# Adafruit_ESP32_Feather_V2.net
KiCad netlist of a schematic drawn in EAGLE
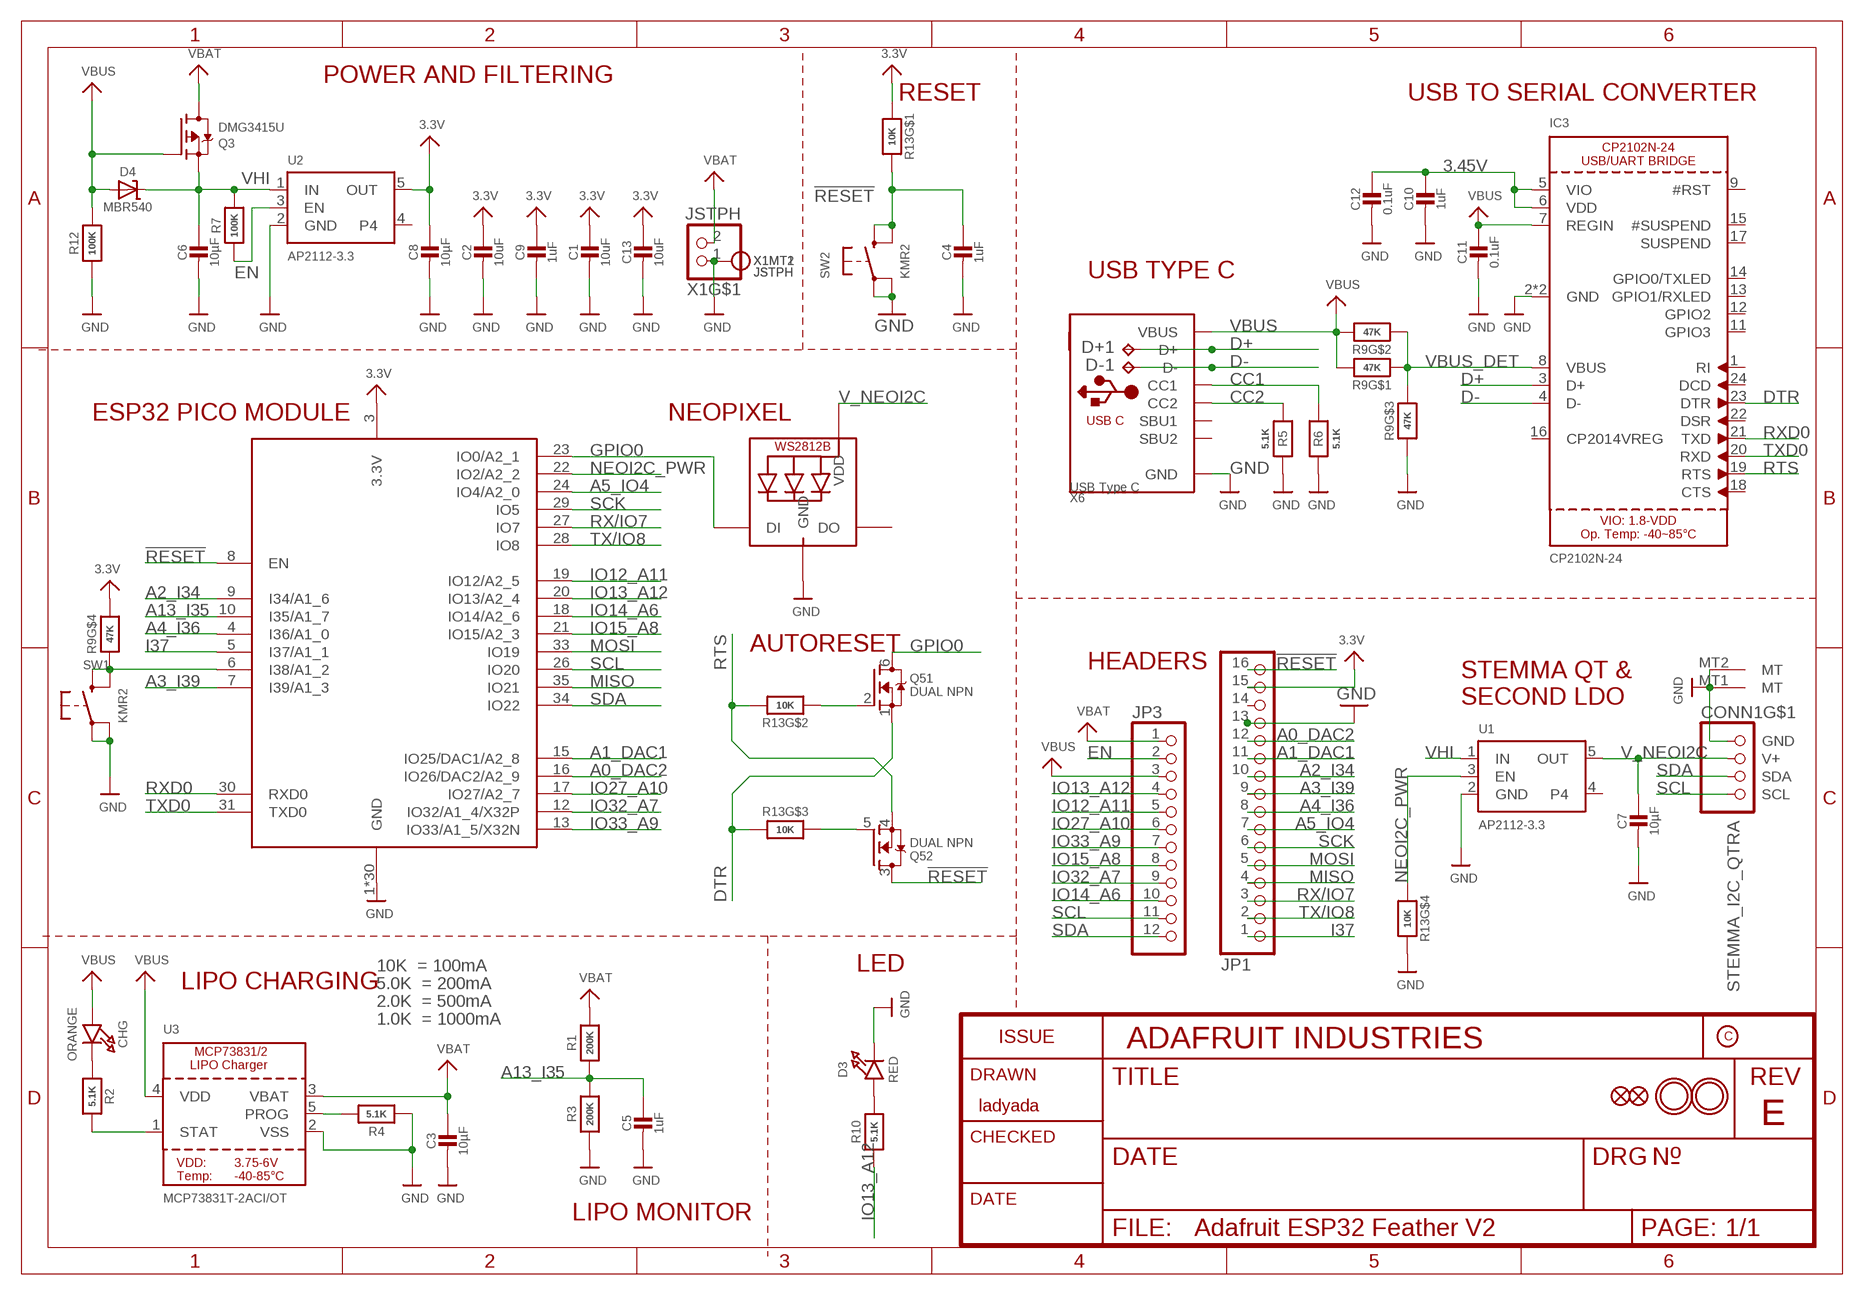
[diagram p0: schematic, sheet 1]

(export (version "E")
  (design (tool "Eeschema 10.0.6"))
  (components
    (comp (ref "C1")
      (value "10uF")
      (footprint "eagle-import:0805-NO")
      (libsource (lib "eagle-import") (part "CAP_CERAMIC0805-NOOUTLINE"))
    )
    (comp (ref "C2")
      (value "10uF")
      (footprint "eagle-import:0805-NO")
      (libsource (lib "eagle-import") (part "CAP_CERAMIC0805-NOOUTLINE"))
    )
    (comp (ref "C3")
      (value "10µF")
      (footprint "eagle-import:0805-NO")
      (libsource (lib "eagle-import") (part "CAP_CERAMIC0805-NOOUTLINE"))
    )
    (comp (ref "C4")
      (value "1uF")
      (footprint "eagle-import:0603-NO")
      (libsource (lib "eagle-import") (part "CAP_CERAMIC0603_NO"))
    )
    (comp (ref "C5")
      (value "1uF")
      (footprint "eagle-import:0603-NO")
      (libsource (lib "eagle-import") (part "CAP_CERAMIC0603_NO"))
    )
    (comp (ref "C6")
      (value "10µF")
      (footprint "eagle-import:0805-NO")
      (libsource (lib "eagle-import") (part "CAP_CERAMIC0805-NOOUTLINE"))
    )
    (comp (ref "C7")
      (value "10µF")
      (footprint "eagle-import:0805-NO")
      (libsource (lib "eagle-import") (part "CAP_CERAMIC0805-NOOUTLINE"))
    )
    (comp (ref "C8")
      (value "10µF")
      (footprint "eagle-import:0805-NO")
      (fields (field (name "REV") "F"))
      (libsource (lib "eagle-import") (part "CAP_CERAMIC0805-NOOUTLINE"))
    )
    (comp (ref "C9")
      (value "1uF")
      (footprint "eagle-import:0603-NO")
      (libsource (lib "eagle-import") (part "CAP_CERAMIC0603_NO"))
    )
    (comp (ref "C10")
      (value "1uF")
      (footprint "eagle-import:0603-NO")
      (libsource (lib "eagle-import") (part "CAP_CERAMIC0603_NO"))
    )
    (comp (ref "C11")
      (value "0.1uF")
      (footprint "eagle-import:0603-NO")
      (libsource (lib "eagle-import") (part "CAP_CERAMIC0603_NO"))
    )
    (comp (ref "C12")
      (value "0.1uF")
      (footprint "eagle-import:0603-NO")
      (libsource (lib "eagle-import") (part "CAP_CERAMIC0603_NO"))
    )
    (comp (ref "C13")
      (value "10uF")
      (footprint "eagle-import:0805-NO")
      (libsource (lib "eagle-import") (part "CAP_CERAMIC0805-NOOUTLINE"))
    )
    (comp (ref "CHG")
      (value "ORANGE")
      (footprint "eagle-import:CHIPLED_0603_NOOUTLINE")
      (libsource (lib "eagle-import") (part "LED0603_NOOUTLINE"))
    )
    (comp (ref "CONN1")
      (value "STEMMA_I2C_QTRA")
      (footprint "eagle-import:JST_SH4_RA")
      (libsource (lib "eagle-import") (part "STEMMA_I2C_QTRA"))
    )
    (comp (ref "D+1")
      (value "TPB1,27")
      (footprint "eagle-import:B1,27")
      (libsource (lib "eagle-import") (part "TPB1,27"))
    )
    (comp (ref "D-1")
      (value "TPB1,27")
      (footprint "eagle-import:B1,27")
      (libsource (lib "eagle-import") (part "TPB1,27"))
    )
    (comp (ref "D3")
      (value "RED")
      (footprint "eagle-import:CHIPLED_0603_NOOUTLINE")
      (libsource (lib "eagle-import") (part "LED0603_NOOUTLINE"))
    )
    (comp (ref "D4")
      (value "MBR540")
      (footprint "eagle-import:SOD-123")
      (libsource (lib "eagle-import") (part "DIODE-SCHOTTKYSOD-123"))
    )
    (comp (ref "IC3")
      (value "CP2102N-24")
      (footprint "eagle-import:QFN24_4MM_SMSC")
      (libsource (lib "eagle-import") (part "CP2102N-24"))
    )
    (comp (ref "JP1")
      (value "HEADER-1X16ROUND")
      (footprint "eagle-import:1X16_ROUND")
      (libsource (lib "eagle-import") (part "HEADER-1X16ROUND"))
    )
    (comp (ref "JP3")
      (value "HEADER-1X12")
      (footprint "eagle-import:1X12_ROUND")
      (libsource (lib "eagle-import") (part "HEADER-1X12"))
    )
    (comp (ref "LED1")
      (value "WS2812B3535")
      (footprint "eagle-import:LED3535")
      (libsource (lib "eagle-import") (part "WS2812B3535"))
    )
    (comp (ref "Q3")
      (value "DMG3415U")
      (footprint "eagle-import:SOT23-R")
      (libsource (lib "eagle-import") (part "MOSFET-P"))
    )
    (comp (ref "Q5")
      (value "DUAL NPN")
      (footprint "eagle-import:SOT363")
      (libsource (lib "eagle-import") (part "MOSFET-N_DUAL"))
    )
    (comp (ref "R1")
      (value "200K")
      (footprint "eagle-import:0603-NO")
      (libsource (lib "eagle-import") (part "RESISTOR_0603_NOOUT"))
    )
    (comp (ref "R2")
      (value "5.1K")
      (footprint "eagle-import:0603-NO")
      (libsource (lib "eagle-import") (part "RESISTOR_0603_NOOUT"))
    )
    (comp (ref "R3")
      (value "200K")
      (footprint "eagle-import:0603-NO")
      (libsource (lib "eagle-import") (part "RESISTOR_0603_NOOUT"))
    )
    (comp (ref "R4")
      (value "5.1K")
      (footprint "eagle-import:0603-NO")
      (libsource (lib "eagle-import") (part "RESISTOR_0603_NOOUT"))
    )
    (comp (ref "R5")
      (value "5.1K")
      (footprint "eagle-import:0603-NO")
      (libsource (lib "eagle-import") (part "RESISTOR_0603_NOOUT"))
    )
    (comp (ref "R6")
      (value "5.1K")
      (footprint "eagle-import:0603-NO")
      (libsource (lib "eagle-import") (part "RESISTOR_0603_NOOUT"))
    )
    (comp (ref "R7")
      (value "100K")
      (footprint "eagle-import:0603-NO")
      (libsource (lib "eagle-import") (part "RESISTOR_0603_NOOUT"))
    )
    (comp (ref "R9")
      (value "47K")
      (footprint "eagle-import:RESPACK_4X0603")
      (libsource (lib "eagle-import") (part "RESISTOR_4PACK"))
    )
    (comp (ref "R10")
      (value "5.1K")
      (footprint "eagle-import:0603-NO")
      (libsource (lib "eagle-import") (part "RESISTOR_0603_NOOUT"))
    )
    (comp (ref "R12")
      (value "100K")
      (footprint "eagle-import:0603-NO")
      (libsource (lib "eagle-import") (part "RESISTOR_0603_NOOUT"))
    )
    (comp (ref "R13")
      (value "10K")
      (footprint "eagle-import:RESPACK_4X0603")
      (libsource (lib "eagle-import") (part "RESISTOR_4PACK"))
    )
    (comp (ref "SW1")
      (value "KMR2")
      (footprint "eagle-import:BTN_KMR2_4.6X2.8")
      (libsource (lib "eagle-import") (part "SWITCH_TACT_SMT4.6X2.8"))
    )
    (comp (ref "SW2")
      (value "KMR2")
      (footprint "eagle-import:BTN_KMR2_4.6X2.8")
      (libsource (lib "eagle-import") (part "SWITCH_TACT_SMT4.6X2.8"))
    )
    (comp (ref "U$31")
      (value "MOUNTINGHOLE2.5")
      (footprint "eagle-import:MOUNTINGHOLE_2.5_PLATED")
      (libsource (lib "eagle-import") (part "MOUNTINGHOLE2.5"))
    )
    (comp (ref "U$32")
      (value "MOUNTINGHOLE2.5")
      (footprint "eagle-import:MOUNTINGHOLE_2.5_PLATED")
      (libsource (lib "eagle-import") (part "MOUNTINGHOLE2.5"))
    )
    (comp (ref "U$34")
      (value "FIDUCIAL_1MM")
      (footprint "eagle-import:FIDUCIAL_1MM")
      (libsource (lib "eagle-import") (part "FIDUCIAL_1MM"))
    )
    (comp (ref "U$35")
      (value "FIDUCIAL_1MM")
      (footprint "eagle-import:FIDUCIAL_1MM")
      (libsource (lib "eagle-import") (part "FIDUCIAL_1MM"))
    )
    (comp (ref "U1")
      (value "AP2112-3.3")
      (footprint "eagle-import:SOT23-5")
      (libsource (lib "eagle-import") (part "VREG_SOT23-5"))
    )
    (comp (ref "U2")
      (value "AP2112-3.3")
      (footprint "eagle-import:SOT23-5")
      (libsource (lib "eagle-import") (part "VREG_SOT23-5"))
    )
    (comp (ref "U3")
      (value "MCP73831T-2ACI/OT")
      (footprint "eagle-import:SOT23-5")
      (libsource (lib "eagle-import") (part "MCP73831/2"))
    )
    (comp (ref "X1")
      (value "JSTPH")
      (footprint "eagle-import:JSTPH2_BATT")
      (libsource (lib "eagle-import") (part "CON_JST_PH_2PIN_MT_BATT"))
    )
    (comp (ref "X3")
      (value "ESP32-PICO-MINI-02MINI")
      (footprint "eagle-import:ESP32-PICO-MINI")
      (libsource (lib "eagle-import") (part "ESP32-PICO-MINI-02MINI"))
    )
    (comp (ref "X6")
      (value "USB Type C")
      (footprint "eagle-import:USB_C_CUSB31-CFM2AX-01-X")
      (libsource (lib "eagle-import") (part "USB_C"))
    )
  )
  (nets
    (net (code "1") (name "/3.45V") (class "Default")
      (node (ref "C10") (pin "1") (pinfunction "1_1") (pintype "passive"))
      (node (ref "C12") (pin "1") (pinfunction "1_1") (pintype "passive"))
      (node (ref "IC3") (pin "5") (pinfunction "VIO_5") (pintype "power_in"))
      (node (ref "IC3") (pin "6") (pinfunction "VDD_6") (pintype "power_in"))
    )
    (net (code "2") (name "/A0_DAC2") (class "Default")
      (node (ref "JP1") (pin "12") (pinfunction "12_12") (pintype "passive"))
      (node (ref "X3") (pin "16") (pinfunction "IO26/DAC2/A2_9_16") (pintype "bidirectional"))
    )
    (net (code "3") (name "/A1_DAC1") (class "Default")
      (node (ref "JP1") (pin "11") (pinfunction "11_11") (pintype "passive"))
      (node (ref "X3") (pin "15") (pinfunction "IO25/DAC1/A2_8_15") (pintype "bidirectional"))
    )
    (net (code "4") (name "/A2_I34") (class "Default")
      (node (ref "JP1") (pin "10") (pinfunction "10_10") (pintype "passive"))
      (node (ref "X3") (pin "9") (pinfunction "I34/A1_6_9") (pintype "input"))
    )
    (net (code "5") (name "/A3_I39") (class "Default")
      (node (ref "JP1") (pin "9") (pinfunction "9_9") (pintype "passive"))
      (node (ref "X3") (pin "7") (pinfunction "I39/A1_3_7") (pintype "input"))
    )
    (net (code "6") (name "/A4_I36") (class "Default")
      (node (ref "JP1") (pin "8") (pinfunction "8_8") (pintype "passive"))
      (node (ref "X3") (pin "4") (pinfunction "I36/A1_0_4") (pintype "input"))
    )
    (net (code "7") (name "/A5_IO4") (class "Default")
      (node (ref "JP1") (pin "7") (pinfunction "7_7") (pintype "passive"))
      (node (ref "X3") (pin "24") (pinfunction "IO4/A2_0_24") (pintype "bidirectional"))
    )
    (net (code "8") (name "/A13_I35") (class "Default")
      (node (ref "C5") (pin "1") (pinfunction "1_1") (pintype "passive"))
      (node (ref "R1") (pin "1") (pinfunction "1_1") (pintype "passive"))
      (node (ref "R3") (pin "2") (pinfunction "2_2") (pintype "passive"))
      (node (ref "X3") (pin "10") (pinfunction "I35/A1_7_10") (pintype "input"))
    )
    (net (code "9") (name "/CC1") (class "Default")
      (node (ref "R6") (pin "2") (pinfunction "2_2") (pintype "passive"))
      (node (ref "X6") (pin "A5") (pinfunction "CC1_A5") (pintype "bidirectional"))
    )
    (net (code "10") (name "/CC2") (class "Default")
      (node (ref "R5") (pin "2") (pinfunction "2_2") (pintype "passive"))
      (node (ref "X6") (pin "B5") (pinfunction "CC2_B5") (pintype "bidirectional"))
    )
    (net (code "11") (name "/D+") (class "Default")
      (node (ref "D+1") (pin "TP") (pinfunction "TP_TP") (pintype "input"))
      (node (ref "IC3") (pin "3") (pinfunction "D+_3") (pintype "bidirectional"))
      (node (ref "X6") (pin "A6") (pinfunction "D+_A6") (pintype "bidirectional"))
      (node (ref "X6") (pin "B6") (pinfunction "D+_B6") (pintype "bidirectional"))
    )
    (net (code "12") (name "/D-") (class "Default")
      (node (ref "D-1") (pin "TP") (pinfunction "TP_TP") (pintype "input"))
      (node (ref "IC3") (pin "4") (pinfunction "D-_4") (pintype "bidirectional"))
      (node (ref "X6") (pin "A7") (pinfunction "D-_A7") (pintype "bidirectional"))
      (node (ref "X6") (pin "B7") (pinfunction "D-_B7") (pintype "bidirectional"))
    )
    (net (code "13") (name "/DTR") (class "Default")
      (node (ref "IC3") (pin "23") (pinfunction "DTR_23") (pintype "output"))
      (node (ref "Q5") (pin "1") (pinfunction "S_1") (pintype "bidirectional"))
      (node (ref "R13") (pin "3") (pinfunction "1_3") (pintype "passive"))
    )
    (net (code "14") (name "/EN") (class "Default")
      (node (ref "JP3") (pin "2") (pinfunction "2_2") (pintype "passive"))
      (node (ref "R7") (pin "1") (pinfunction "1_1") (pintype "passive"))
      (node (ref "U2") (pin "3") (pinfunction "EN_3") (pintype "input"))
    )
    (net (code "15") (name "/GPIO0") (class "Default")
      (node (ref "LED1") (pin "1") (pinfunction "DI_1") (pintype "input"))
      (node (ref "Q5") (pin "6") (pinfunction "D_6") (pintype "bidirectional"))
      (node (ref "X3") (pin "23") (pinfunction "IO0/A2_1_23") (pintype "bidirectional"))
    )
    (net (code "16") (name "/I37") (class "Default")
      (node (ref "JP1") (pin "1") (pinfunction "1_1") (pintype "passive"))
      (node (ref "X3") (pin "5") (pinfunction "I37/A1_1_5") (pintype "input"))
    )
    (net (code "17") (name "/IO12_A11") (class "Default")
      (node (ref "JP3") (pin "5") (pinfunction "5_5") (pintype "passive"))
      (node (ref "X3") (pin "19") (pinfunction "IO12/A2_5_19") (pintype "bidirectional"))
    )
    (net (code "18") (name "/IO13_A12") (class "Default")
      (node (ref "JP3") (pin "4") (pinfunction "4_4") (pintype "passive"))
      (node (ref "R10") (pin "1") (pinfunction "1_1") (pintype "passive"))
      (node (ref "X3") (pin "20") (pinfunction "IO13/A2_4_20") (pintype "bidirectional"))
    )
    (net (code "19") (name "/IO14_A6") (class "Default")
      (node (ref "JP3") (pin "10") (pinfunction "10_10") (pintype "passive"))
      (node (ref "X3") (pin "18") (pinfunction "IO14/A2_6_18") (pintype "bidirectional"))
    )
    (net (code "20") (name "/IO15_A8") (class "Default")
      (node (ref "JP3") (pin "8") (pinfunction "8_8") (pintype "passive"))
      (node (ref "X3") (pin "21") (pinfunction "IO15/A2_3_21") (pintype "bidirectional"))
    )
    (net (code "21") (name "/IO27_A10") (class "Default")
      (node (ref "JP3") (pin "6") (pinfunction "6_6") (pintype "passive"))
      (node (ref "X3") (pin "17") (pinfunction "IO27/A2_7_17") (pintype "bidirectional"))
    )
    (net (code "22") (name "/IO32_A7") (class "Default")
      (node (ref "JP3") (pin "9") (pinfunction "9_9") (pintype "passive"))
      (node (ref "X3") (pin "12") (pinfunction "IO32/A1_4/X32P_12") (pintype "bidirectional"))
    )
    (net (code "23") (name "/IO33_A9") (class "Default")
      (node (ref "JP3") (pin "7") (pinfunction "7_7") (pintype "passive"))
      (node (ref "X3") (pin "13") (pinfunction "IO33/A1_5/X32N_13") (pintype "bidirectional"))
    )
    (net (code "24") (name "/MISO") (class "Default")
      (node (ref "JP1") (pin "4") (pinfunction "4_4") (pintype "passive"))
      (node (ref "X3") (pin "35") (pinfunction "IO21_35") (pintype "bidirectional"))
    )
    (net (code "25") (name "/MOSI") (class "Default")
      (node (ref "JP1") (pin "5") (pinfunction "5_5") (pintype "passive"))
      (node (ref "X3") (pin "33") (pinfunction "IO19_33") (pintype "bidirectional"))
    )
    (net (code "26") (name "/NEOI2C_PWR") (class "Default")
      (node (ref "R13") (pin "4") (pinfunction "1_4") (pintype "passive"))
      (node (ref "U1") (pin "3") (pinfunction "EN_3") (pintype "input"))
      (node (ref "X3") (pin "22") (pinfunction "IO2/A2_2_22") (pintype "bidirectional"))
    )
    (net (code "27") (name "/RTS") (class "Default")
      (node (ref "IC3") (pin "19") (pinfunction "RTS_19") (pintype "output"))
      (node (ref "Q5") (pin "4") (pinfunction "S_4") (pintype "bidirectional"))
      (node (ref "R13") (pin "7") (pinfunction "2_7") (pintype "passive"))
    )
    (net (code "28") (name "/RXD0") (class "Default")
      (node (ref "IC3") (pin "21") (pinfunction "TXD_21") (pintype "output"))
      (node (ref "X3") (pin "30") (pinfunction "RXD0_30") (pintype "input"))
    )
    (net (code "29") (name "/RX{slash}IO7") (class "Default")
      (node (ref "JP1") (pin "3") (pinfunction "3_3") (pintype "passive"))
      (node (ref "X3") (pin "27") (pinfunction "IO7_27") (pintype "bidirectional"))
    )
    (net (code "30") (name "/SCK") (class "Default")
      (node (ref "JP1") (pin "6") (pinfunction "6_6") (pintype "passive"))
      (node (ref "X3") (pin "29") (pinfunction "IO5_29") (pintype "bidirectional"))
    )
    (net (code "31") (name "/SCL") (class "Default")
      (node (ref "CONN1") (pin "4") (pinfunction "SCL_4") (pintype "passive"))
      (node (ref "JP3") (pin "11") (pinfunction "11_11") (pintype "passive"))
      (node (ref "X3") (pin "26") (pinfunction "IO20_26") (pintype "bidirectional"))
    )
    (net (code "32") (name "/SDA") (class "Default")
      (node (ref "CONN1") (pin "3") (pinfunction "SDA_3") (pintype "passive"))
      (node (ref "JP3") (pin "12") (pinfunction "12_12") (pintype "passive"))
      (node (ref "X3") (pin "34") (pinfunction "IO22_34") (pintype "bidirectional"))
    )
    (net (code "33") (name "/TXD0") (class "Default")
      (node (ref "IC3") (pin "20") (pinfunction "RXD_20") (pintype "input"))
      (node (ref "X3") (pin "31") (pinfunction "TXD0_31") (pintype "output"))
    )
    (net (code "34") (name "/TX{slash}IO8") (class "Default")
      (node (ref "JP1") (pin "2") (pinfunction "2_2") (pintype "passive"))
      (node (ref "X3") (pin "28") (pinfunction "IO8_28") (pintype "bidirectional"))
    )
    (net (code "35") (name "/VBUS_DET") (class "Default")
      (node (ref "IC3") (pin "8") (pinfunction "VBUS_8") (pintype "power_in"))
      (node (ref "R9") (pin "1") (pinfunction "1_1") (pintype "passive"))
      (node (ref "R9") (pin "2") (pinfunction "1_2") (pintype "passive"))
      (node (ref "R9") (pin "6") (pinfunction "2_6") (pintype "passive"))
    )
    (net (code "36") (name "/VHI") (class "Default")
      (node (ref "C6") (pin "1") (pinfunction "1_1") (pintype "passive"))
      (node (ref "D4") (pin "C") (pinfunction "C_C") (pintype "passive"))
      (node (ref "Q3") (pin "2") (pinfunction "S_2") (pintype "passive"))
      (node (ref "R7") (pin "2") (pinfunction "2_2") (pintype "passive"))
      (node (ref "U1") (pin "1") (pinfunction "IN_1") (pintype "power_in"))
      (node (ref "U2") (pin "1") (pinfunction "IN_1") (pintype "power_in"))
    )
    (net (code "37") (name "/V_NEOI2C") (class "Default")
      (node (ref "C7") (pin "1") (pinfunction "1_1") (pintype "passive"))
      (node (ref "CONN1") (pin "2") (pinfunction "V+_2") (pintype "passive"))
      (node (ref "LED1") (pin "2") (pinfunction "VDD_2") (pintype "power_in"))
      (node (ref "U1") (pin "5") (pinfunction "OUT_5") (pintype "power_in"))
    )
    (net (code "38") (name "/~{RESET}") (class "Default")
      (node (ref "C4") (pin "1") (pinfunction "1_1") (pintype "passive"))
      (node (ref "JP1") (pin "16") (pinfunction "16_16") (pintype "passive"))
      (node (ref "Q5") (pin "3") (pinfunction "D_3") (pintype "bidirectional"))
      (node (ref "R13") (pin "8") (pinfunction "2_8") (pintype "passive"))
      (node (ref "SW2") (pin "B") (pinfunction "S_B") (pintype "passive"))
      (node (ref "SW2") (pin "B'") (pinfunction "S1_B'") (pintype "passive"))
      (node (ref "X3") (pin "8") (pinfunction "EN_8") (pintype "input"))
    )
    (net (code "39") (name "3.3V") (class "Default")
      (node (ref "C1") (pin "1") (pinfunction "1_1") (pintype "passive"))
      (node (ref "C13") (pin "1") (pinfunction "1_1") (pintype "passive"))
      (node (ref "C2") (pin "1") (pinfunction "1_1") (pintype "passive"))
      (node (ref "C8") (pin "1") (pinfunction "1_1") (pintype "passive"))
      (node (ref "C9") (pin "1") (pinfunction "1_1") (pintype "passive"))
      (node (ref "JP1") (pin "15") (pinfunction "15_15") (pintype "passive"))
      (node (ref "R13") (pin "1") (pinfunction "1_1") (pintype "passive"))
      (node (ref "R9") (pin "5") (pinfunction "2_5") (pintype "passive"))
      (node (ref "U2") (pin "5") (pinfunction "OUT_5") (pintype "power_in"))
      (node (ref "X3") (pin "3") (pinfunction "3.3V_3") (pintype "passive"))
    )
    (net (code "40") (name "GND") (class "Default")
      (node (ref "C1") (pin "2") (pinfunction "2_2") (pintype "passive"))
      (node (ref "C10") (pin "2") (pinfunction "2_2") (pintype "passive"))
      (node (ref "C11") (pin "2") (pinfunction "2_2") (pintype "passive"))
      (node (ref "C12") (pin "2") (pinfunction "2_2") (pintype "passive"))
      (node (ref "C13") (pin "2") (pinfunction "2_2") (pintype "passive"))
      (node (ref "C2") (pin "2") (pinfunction "2_2") (pintype "passive"))
      (node (ref "C3") (pin "2") (pinfunction "2_2") (pintype "passive"))
      (node (ref "C4") (pin "2") (pinfunction "2_2") (pintype "passive"))
      (node (ref "C5") (pin "2") (pinfunction "2_2") (pintype "passive"))
      (node (ref "C6") (pin "2") (pinfunction "2_2") (pintype "passive"))
      (node (ref "C7") (pin "2") (pinfunction "2_2") (pintype "passive"))
      (node (ref "C8") (pin "2") (pinfunction "2_2") (pintype "passive"))
      (node (ref "C9") (pin "2") (pinfunction "2_2") (pintype "passive"))
      (node (ref "CONN1") (pin "1") (pinfunction "GND_1") (pintype "passive"))
      (node (ref "CONN1") (pin "MT1") (pinfunction "MT_MT1") (pintype "bidirectional"))
      (node (ref "CONN1") (pin "MT2") (pinfunction "MT_MT2") (pintype "bidirectional"))
      (node (ref "D3") (pin "C") (pinfunction "C_C") (pintype "passive"))
      (node (ref "IC3") (pin "2") (pinfunction "GND_2") (pintype "power_in"))
      (node (ref "IC3") (pin "THERM") (pinfunction "GND_THERM") (pintype "power_in"))
      (node (ref "JP1") (pin "13") (pinfunction "13_13") (pintype "passive"))
      (node (ref "LED1") (pin "4") (pinfunction "GND_4") (pintype "power_in"))
      (node (ref "R12") (pin "1") (pinfunction "1_1") (pintype "passive"))
      (node (ref "R13") (pin "5") (pinfunction "2_5") (pintype "passive"))
      (node (ref "R3") (pin "1") (pinfunction "1_1") (pintype "passive"))
      (node (ref "R4") (pin "1") (pinfunction "1_1") (pintype "passive"))
      (node (ref "R5") (pin "1") (pinfunction "1_1") (pintype "passive"))
      (node (ref "R6") (pin "1") (pinfunction "1_1") (pintype "passive"))
      (node (ref "R9") (pin "3") (pinfunction "1_3") (pintype "passive"))
      (node (ref "SW1") (pin "A") (pinfunction "P_A") (pintype "passive"))
      (node (ref "SW1") (pin "A'") (pinfunction "P1_A'") (pintype "passive"))
      (node (ref "SW2") (pin "A") (pinfunction "P_A") (pintype "passive"))
      (node (ref "SW2") (pin "A'") (pinfunction "P1_A'") (pintype "passive"))
      (node (ref "U1") (pin "2") (pinfunction "GND_2") (pintype "power_in"))
      (node (ref "U2") (pin "2") (pinfunction "GND_2") (pintype "power_in"))
      (node (ref "U3") (pin "2") (pinfunction "VSS_2") (pintype "power_in"))
      (node (ref "X1") (pin "1") (pinfunction "1_1") (pintype "passive"))
      (node (ref "X1") (pin "NC1") (pinfunction "P$1_NC1") (pintype "bidirectional"))
      (node (ref "X1") (pin "NC2") (pinfunction "P$1_NC2") (pintype "bidirectional"))
      (node (ref "X3") (pin "1") (pinfunction "GND_1") (pintype "passive"))
      (node (ref "X3") (pin "11") (pinfunction "GND_11") (pintype "passive"))
      (node (ref "X3") (pin "14") (pinfunction "GND_14") (pintype "passive"))
      (node (ref "X3") (pin "2") (pinfunction "GND_2") (pintype "passive"))
      (node (ref "X3") (pin "36") (pinfunction "GND_36") (pintype "passive"))
      (node (ref "X3") (pin "37") (pinfunction "GND_37") (pintype "passive"))
      (node (ref "X3") (pin "38") (pinfunction "GND_38") (pintype "passive"))
      (node (ref "X3") (pin "39") (pinfunction "GND_39") (pintype "passive"))
      (node (ref "X3") (pin "40") (pinfunction "GND_40") (pintype "passive"))
      (node (ref "X3") (pin "41") (pinfunction "GND_41") (pintype "passive"))
      (node (ref "X3") (pin "42") (pinfunction "GND_42") (pintype "passive"))
      (node (ref "X3") (pin "43") (pinfunction "GND_43") (pintype "passive"))
      (node (ref "X3") (pin "44") (pinfunction "GND_44") (pintype "passive"))
      (node (ref "X3") (pin "45") (pinfunction "GND_45") (pintype "passive"))
      (node (ref "X3") (pin "46") (pinfunction "GND_46") (pintype "passive"))
      (node (ref "X3") (pin "47") (pinfunction "GND_47") (pintype "passive"))
      (node (ref "X3") (pin "48") (pinfunction "GND_48") (pintype "passive"))
      (node (ref "X3") (pin "49") (pinfunction "GND_49") (pintype "passive"))
      (node (ref "X3") (pin "50") (pinfunction "GND_50") (pintype "passive"))
      (node (ref "X3") (pin "51") (pinfunction "GND_51") (pintype "passive"))
      (node (ref "X3") (pin "52") (pinfunction "GND_52") (pintype "passive"))
      (node (ref "X3") (pin "53") (pinfunction "GND_53") (pintype "passive"))
      (node (ref "X3") (pin "54") (pinfunction "GND_54") (pintype "passive"))
      (node (ref "X3") (pin "55") (pinfunction "GND_55") (pintype "passive"))
      (node (ref "X3") (pin "56") (pinfunction "GND_56") (pintype "passive"))
      (node (ref "X3") (pin "57") (pinfunction "GND_57") (pintype "passive"))
      (node (ref "X3") (pin "58") (pinfunction "GND_58") (pintype "passive"))
      (node (ref "X3") (pin "59") (pinfunction "GND_59") (pintype "passive"))
      (node (ref "X3") (pin "60") (pinfunction "GND_60") (pintype "passive"))
      (node (ref "X3") (pin "61") (pinfunction "GND_61") (pintype "passive"))
      (node (ref "X6") (pin "A1B12") (pinfunction "GND_A1B12") (pintype "power_in"))
      (node (ref "X6") (pin "B1A12") (pinfunction "GND_B1A12") (pintype "power_in"))
    )
    (net (code "41") (name "Net-(CHG-PadC)") (class "Default")
      (node (ref "CHG") (pin "C") (pinfunction "C_C") (pintype "passive"))
      (node (ref "R2") (pin "1") (pinfunction "1_1") (pintype "passive"))
    )
    (net (code "42") (name "Net-(D3-PadA)") (class "Default")
      (node (ref "D3") (pin "A") (pinfunction "A_A") (pintype "passive"))
      (node (ref "R10") (pin "2") (pinfunction "2_2") (pintype "passive"))
    )
    (net (code "43") (name "Net-(Q5A-G)") (class "Default")
      (node (ref "Q5") (pin "2") (pinfunction "G_2") (pintype "bidirectional"))
      (node (ref "R13") (pin "2") (pinfunction "1_2") (pintype "passive"))
    )
    (net (code "44") (name "Net-(Q5B-G)") (class "Default")
      (node (ref "Q5") (pin "5") (pinfunction "G_5") (pintype "bidirectional"))
      (node (ref "R13") (pin "6") (pinfunction "2_6") (pintype "passive"))
    )
    (net (code "45") (name "Net-(R9D-1)") (class "Default")
      (node (ref "R9") (pin "4") (pinfunction "1_4") (pintype "passive"))
      (node (ref "SW1") (pin "B") (pinfunction "S_B") (pintype "passive"))
      (node (ref "SW1") (pin "B'") (pinfunction "S1_B'") (pintype "passive"))
      (node (ref "X3") (pin "6") (pinfunction "I38/A1_2_6") (pintype "input"))
    )
    (net (code "46") (name "Net-(U3-PROG)") (class "Default")
      (node (ref "R4") (pin "2") (pinfunction "2_2") (pintype "passive"))
      (node (ref "U3") (pin "5") (pinfunction "PROG_5") (pintype "input"))
    )
    (net (code "47") (name "Net-(U3-STAT)") (class "Default")
      (node (ref "R2") (pin "2") (pinfunction "2_2") (pintype "passive"))
      (node (ref "U3") (pin "1") (pinfunction "STAT_1") (pintype "output"))
    )
    (net (code "48") (name "VBAT") (class "Default")
      (node (ref "C3") (pin "1") (pinfunction "1_1") (pintype "passive"))
      (node (ref "JP3") (pin "1") (pinfunction "1_1") (pintype "passive"))
      (node (ref "Q3") (pin "3") (pinfunction "D_3") (pintype "passive"))
      (node (ref "R1") (pin "2") (pinfunction "2_2") (pintype "passive"))
      (node (ref "U3") (pin "3") (pinfunction "VBAT_3") (pintype "power_in"))
      (node (ref "X1") (pin "2") (pinfunction "2_2") (pintype "passive"))
    )
    (net (code "49") (name "VBUS") (class "Default")
      (node (ref "C11") (pin "1") (pinfunction "1_1") (pintype "passive"))
      (node (ref "CHG") (pin "A") (pinfunction "A_A") (pintype "passive"))
      (node (ref "D4") (pin "A") (pinfunction "A_A") (pintype "passive"))
      (node (ref "IC3") (pin "7") (pinfunction "REGIN_7") (pintype "power_in"))
      (node (ref "JP3") (pin "3") (pinfunction "3_3") (pintype "passive"))
      (node (ref "Q3") (pin "1") (pinfunction "G_1") (pintype "passive"))
      (node (ref "R12") (pin "2") (pinfunction "2_2") (pintype "passive"))
      (node (ref "R9") (pin "7") (pinfunction "2_7") (pintype "passive"))
      (node (ref "R9") (pin "8") (pinfunction "2_8") (pintype "passive"))
      (node (ref "U3") (pin "4") (pinfunction "VDD_4") (pintype "power_in"))
      (node (ref "X6") (pin "A4B9") (pinfunction "VBUS_A4B9") (pintype "power_in"))
      (node (ref "X6") (pin "B4A9") (pinfunction "VBUS_B4A9") (pintype "power_in"))
    )
    (net (code "50") (name "unconnected-(IC3-#RST-Pad9)") (class "Default")
      (node (ref "IC3") (pin "9") (pinfunction "#RST_9") (pintype "bidirectional"))
    )
    (net (code "51") (name "unconnected-(IC3-#SUSPEND-Pad15)") (class "Default")
      (node (ref "IC3") (pin "15") (pinfunction "#SUSPEND_15") (pintype "output"))
    )
    (net (code "52") (name "unconnected-(IC3-CP2014VREG-Pad16)") (class "Default")
      (node (ref "IC3") (pin "16") (pinfunction "CP2014VREG_16") (pintype "passive"))
    )
    (net (code "53") (name "unconnected-(IC3-CTS-Pad18)") (class "Default")
      (node (ref "IC3") (pin "18") (pinfunction "CTS_18") (pintype "input"))
    )
    (net (code "54") (name "unconnected-(IC3-DCD-Pad24)") (class "Default")
      (node (ref "IC3") (pin "24") (pinfunction "DCD_24") (pintype "input"))
    )
    (net (code "55") (name "unconnected-(IC3-DSR-Pad22)") (class "Default")
      (node (ref "IC3") (pin "22") (pinfunction "DSR_22") (pintype "input"))
    )
    (net (code "56") (name "unconnected-(IC3-GPIO0{slash}TXLED-Pad14)") (class "Default")
      (node (ref "IC3") (pin "14") (pinfunction "GPIO0/TXLED_14") (pintype "bidirectional"))
    )
    (net (code "57") (name "unconnected-(IC3-GPIO1{slash}RXLED-Pad13)") (class "Default")
      (node (ref "IC3") (pin "13") (pinfunction "GPIO1/RXLED_13") (pintype "bidirectional"))
    )
    (net (code "58") (name "unconnected-(IC3-GPIO2-Pad12)") (class "Default")
      (node (ref "IC3") (pin "12") (pinfunction "GPIO2_12") (pintype "bidirectional"))
    )
    (net (code "59") (name "unconnected-(IC3-GPIO3-Pad11)") (class "Default")
      (node (ref "IC3") (pin "11") (pinfunction "GPIO3_11") (pintype "bidirectional"))
    )
    (net (code "60") (name "unconnected-(IC3-RI-Pad1)") (class "Default")
      (node (ref "IC3") (pin "1") (pinfunction "RI_1") (pintype "input"))
    )
    (net (code "61") (name "unconnected-(IC3-SUSPEND-Pad17)") (class "Default")
      (node (ref "IC3") (pin "17") (pinfunction "SUSPEND_17") (pintype "output"))
    )
    (net (code "62") (name "unconnected-(JP1-Pad14)") (class "Default")
      (node (ref "JP1") (pin "14") (pinfunction "14_14") (pintype "passive"))
    )
    (net (code "63") (name "unconnected-(LED1-DO-Pad3)") (class "Default")
      (node (ref "LED1") (pin "3") (pinfunction "DO_3") (pintype "output"))
    )
    (net (code "64") (name "unconnected-(U1-P4-Pad4)") (class "Default")
      (node (ref "U1") (pin "4") (pinfunction "P4_4") (pintype "bidirectional"))
    )
    (net (code "65") (name "unconnected-(U2-P4-Pad4)") (class "Default")
      (node (ref "U2") (pin "4") (pinfunction "P4_4") (pintype "bidirectional"))
    )
    (net (code "66") (name "unconnected-(X6-SBU1-PadA8)") (class "Default")
      (node (ref "X6") (pin "A8") (pinfunction "SBU1_A8") (pintype "bidirectional"))
    )
    (net (code "67") (name "unconnected-(X6-SBU2-PadB8)") (class "Default")
      (node (ref "X6") (pin "B8") (pinfunction "SBU2_B8") (pintype "bidirectional"))
    )
  )
)
